# OperantFEDv9.net
KiCad netlist of a schematic drawn in EAGLE
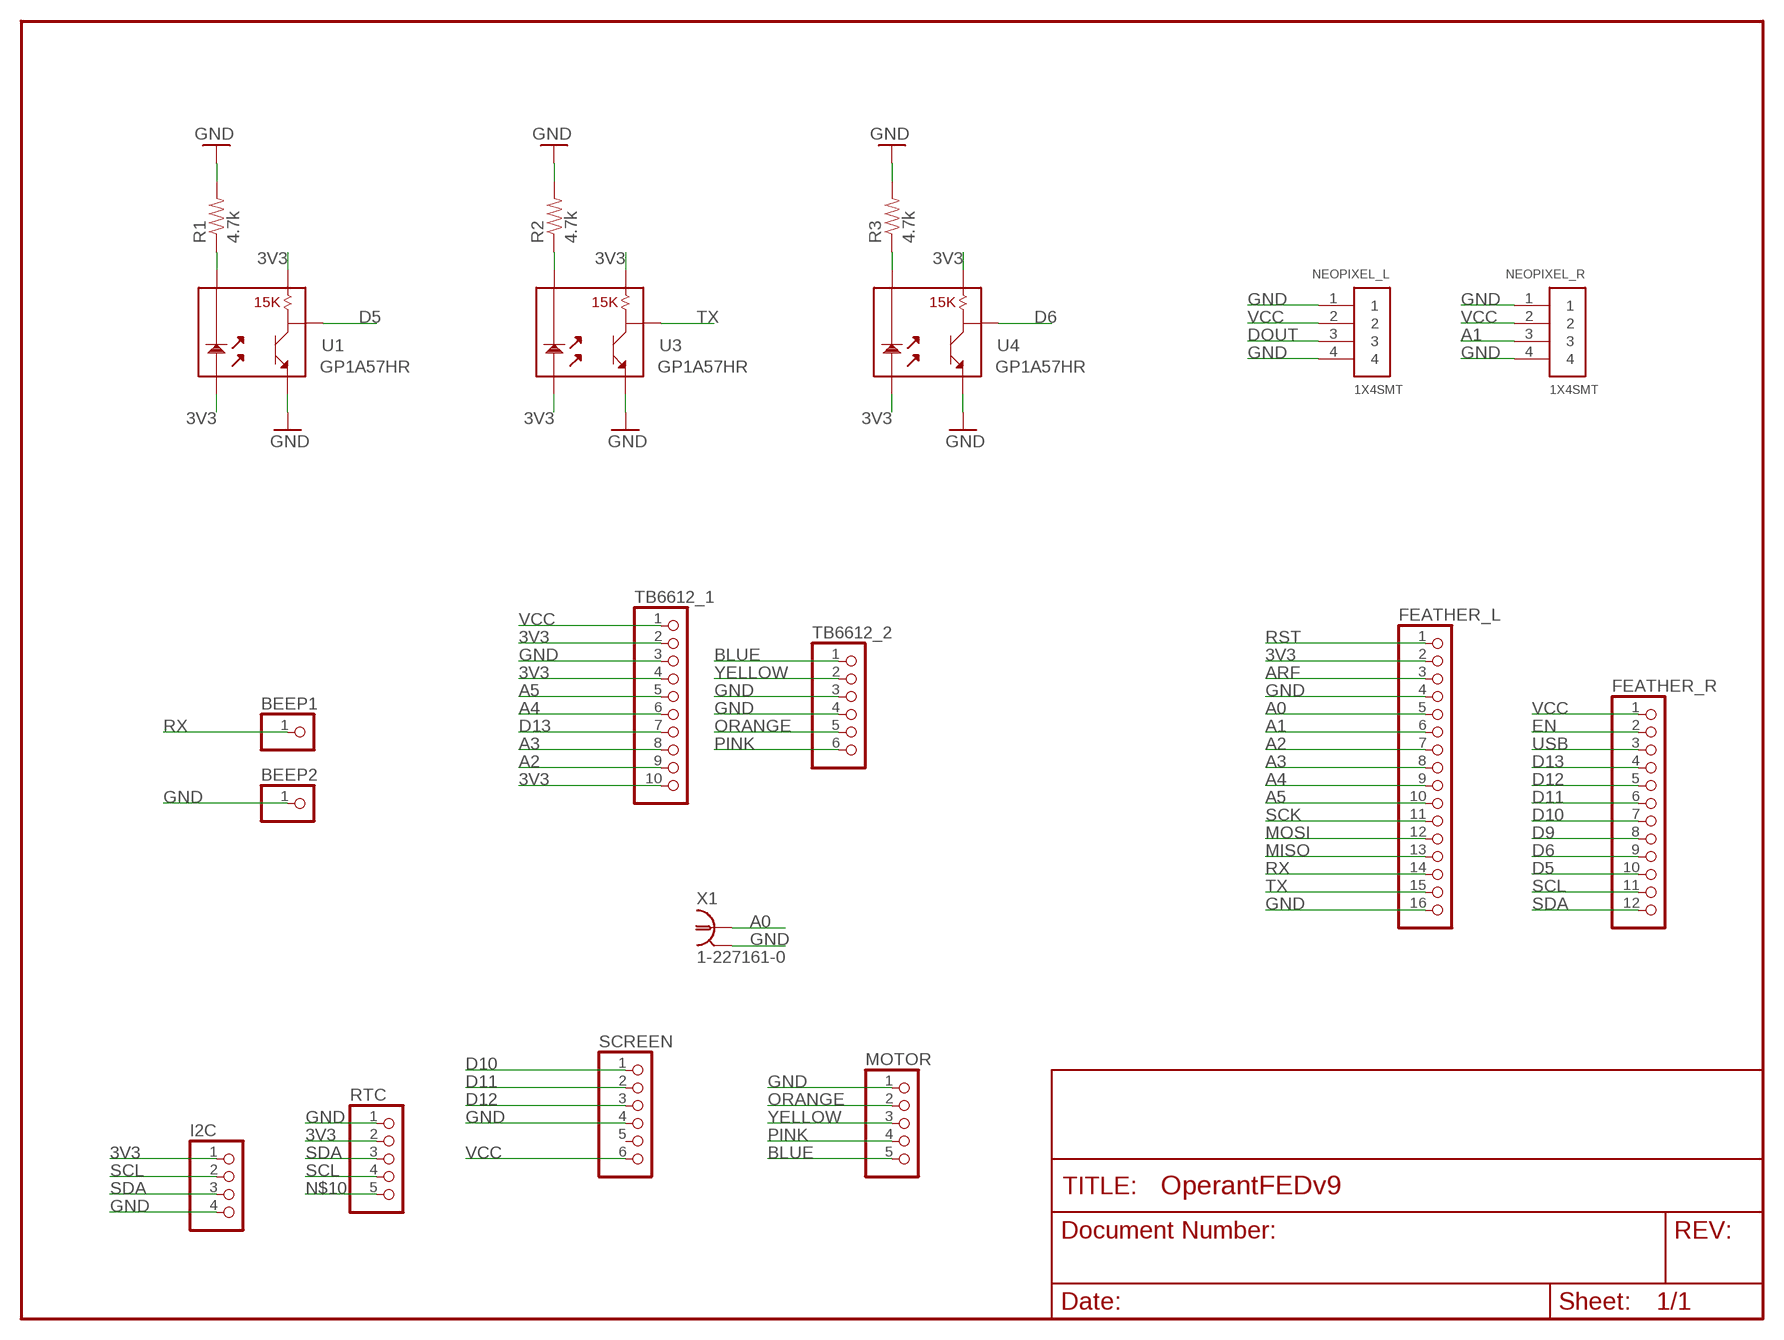
[diagram p0: schematic, sheet 1]

(export (version "E")
  (design (tool "Eeschema 10.0.6"))
  (components
    (comp (ref "BEEP1")
      (value "PINHD-1X1")
      (footprint "eagle-import:1X01")
      (libsource (lib "eagle-import") (part "PINHD-1X1"))
    )
    (comp (ref "BEEP2")
      (value "PINHD-1X1")
      (footprint "eagle-import:1X01")
      (libsource (lib "eagle-import") (part "PINHD-1X1"))
    )
    (comp (ref "FEATHER_L")
      (value "PINHD-1X16")
      (footprint "eagle-import:1X16")
      (libsource (lib "eagle-import") (part "PINHD-1X16"))
    )
    (comp (ref "FEATHER_R")
      (value "PINHD-1X12")
      (footprint "eagle-import:1X12")
      (libsource (lib "eagle-import") (part "PINHD-1X12"))
    )
    (comp (ref "I2C")
      (value "PINHD-1X4")
      (footprint "eagle-import:1X04")
      (libsource (lib "eagle-import") (part "PINHD-1X4"))
    )
    (comp (ref "MOTOR")
      (value "PINHD-1X5")
      (footprint "eagle-import:1X05")
      (libsource (lib "eagle-import") (part "PINHD-1X5"))
    )
    (comp (ref "NEOPIXEL_L")
      (value "1X4SMT")
      (footprint "eagle-import:1X4-SMT")
      (libsource (lib "eagle-import") (part "1X4SMT"))
    )
    (comp (ref "NEOPIXEL_R")
      (value "1X4SMT")
      (footprint "eagle-import:1X4-SMT")
      (libsource (lib "eagle-import") (part "1X4SMT"))
    )
    (comp (ref "R1")
      (value "4.7k")
      (footprint "eagle-import:AXIAL-0.3")
      (libsource (lib "eagle-import") (part "RESISTORPTH1"))
    )
    (comp (ref "R2")
      (value "4.7k")
      (footprint "eagle-import:AXIAL-0.3")
      (libsource (lib "eagle-import") (part "RESISTORPTH1"))
    )
    (comp (ref "R3")
      (value "4.7k")
      (footprint "eagle-import:AXIAL-0.3")
      (libsource (lib "eagle-import") (part "RESISTORPTH1"))
    )
    (comp (ref "RTC")
      (value "PINHD-1X5")
      (footprint "eagle-import:1X05")
      (libsource (lib "eagle-import") (part "PINHD-1X5"))
    )
    (comp (ref "SCREEN")
      (value "PINHD-1X6")
      (footprint "eagle-import:1X06")
      (libsource (lib "eagle-import") (part "PINHD-1X6"))
    )
    (comp (ref "TB6612_1")
      (value "PINHD-1X10")
      (footprint "eagle-import:1X10")
      (libsource (lib "eagle-import") (part "PINHD-1X10"))
    )
    (comp (ref "TB6612_2")
      (value "PINHD-1X6")
      (footprint "eagle-import:1X06")
      (libsource (lib "eagle-import") (part "PINHD-1X6"))
    )
    (comp (ref "U1")
      (value "GP1A57HR")
      (footprint "eagle-import:GP1A57HR")
      (libsource (lib "eagle-import") (part "GP1A57HR"))
    )
    (comp (ref "U3")
      (value "GP1A57HR")
      (footprint "eagle-import:GP1A57HR")
      (libsource (lib "eagle-import") (part "GP1A57HR"))
    )
    (comp (ref "U4")
      (value "GP1A57HR")
      (footprint "eagle-import:GP1A57HR")
      (libsource (lib "eagle-import") (part "GP1A57HR"))
    )
    (comp (ref "X1")
      (value "1-227161-0")
      (footprint "eagle-import:AMP_227161")
      (fields (field (name "MF") "TYCO ELECTRONICS") (field (name "MPN") "1-227161"))
      (libsource (lib "eagle-import") (part "?2271611--0"))
    )
  )
  (nets
    (net (code "1") (name "/3V3") (class "Default")
      (node (ref "FEATHER_L") (pin "2") (pinfunction "2_2") (pintype "passive"))
      (node (ref "I2C") (pin "1") (pinfunction "1_1") (pintype "passive"))
      (node (ref "RTC") (pin "2") (pinfunction "2_2") (pintype "passive"))
      (node (ref "TB6612_1") (pin "10") (pinfunction "10_10") (pintype "passive"))
      (node (ref "TB6612_1") (pin "2") (pinfunction "2_2") (pintype "passive"))
      (node (ref "TB6612_1") (pin "4") (pinfunction "4_4") (pintype "passive"))
      (node (ref "U1") (pin "1") (pinfunction "1_1") (pintype "bidirectional"))
      (node (ref "U1") (pin "3") (pinfunction "3_3") (pintype "bidirectional"))
      (node (ref "U3") (pin "1") (pinfunction "1_1") (pintype "bidirectional"))
      (node (ref "U3") (pin "3") (pinfunction "3_3") (pintype "bidirectional"))
      (node (ref "U4") (pin "1") (pinfunction "1_1") (pintype "bidirectional"))
      (node (ref "U4") (pin "3") (pinfunction "3_3") (pintype "bidirectional"))
    )
    (net (code "2") (name "/A0") (class "Default")
      (node (ref "FEATHER_L") (pin "5") (pinfunction "5_5") (pintype "passive"))
      (node (ref "X1") (pin "1") (pinfunction "1_1") (pintype "passive"))
    )
    (net (code "3") (name "/A1") (class "Default")
      (node (ref "FEATHER_L") (pin "6") (pinfunction "6_6") (pintype "passive"))
      (node (ref "NEOPIXEL_R") (pin "3") (pinfunction "3_3") (pintype "bidirectional"))
    )
    (net (code "4") (name "/A2") (class "Default")
      (node (ref "FEATHER_L") (pin "7") (pinfunction "7_7") (pintype "passive"))
      (node (ref "TB6612_1") (pin "9") (pinfunction "9_9") (pintype "passive"))
    )
    (net (code "5") (name "/A3") (class "Default")
      (node (ref "FEATHER_L") (pin "8") (pinfunction "8_8") (pintype "passive"))
      (node (ref "TB6612_1") (pin "8") (pinfunction "8_8") (pintype "passive"))
    )
    (net (code "6") (name "/A4") (class "Default")
      (node (ref "FEATHER_L") (pin "9") (pinfunction "9_9") (pintype "passive"))
      (node (ref "TB6612_1") (pin "6") (pinfunction "6_6") (pintype "passive"))
    )
    (net (code "7") (name "/A5") (class "Default")
      (node (ref "FEATHER_L") (pin "10") (pinfunction "10_10") (pintype "passive"))
      (node (ref "TB6612_1") (pin "5") (pinfunction "5_5") (pintype "passive"))
    )
    (net (code "8") (name "/ARF") (class "Default")
      (node (ref "FEATHER_L") (pin "3") (pinfunction "3_3") (pintype "passive"))
    )
    (net (code "9") (name "/BLUE") (class "Default")
      (node (ref "MOTOR") (pin "5") (pinfunction "5_5") (pintype "passive"))
      (node (ref "TB6612_2") (pin "1") (pinfunction "1_1") (pintype "passive"))
    )
    (net (code "10") (name "/D5") (class "Default")
      (node (ref "FEATHER_R") (pin "10") (pinfunction "10_10") (pintype "passive"))
      (node (ref "U1") (pin "4") (pinfunction "4_4") (pintype "bidirectional"))
    )
    (net (code "11") (name "/D6") (class "Default")
      (node (ref "FEATHER_R") (pin "9") (pinfunction "9_9") (pintype "passive"))
      (node (ref "U4") (pin "4") (pinfunction "4_4") (pintype "bidirectional"))
    )
    (net (code "12") (name "/D9") (class "Default")
      (node (ref "FEATHER_R") (pin "8") (pinfunction "8_8") (pintype "passive"))
    )
    (net (code "13") (name "/D10") (class "Default")
      (node (ref "FEATHER_R") (pin "7") (pinfunction "7_7") (pintype "passive"))
      (node (ref "SCREEN") (pin "1") (pinfunction "1_1") (pintype "passive"))
    )
    (net (code "14") (name "/D11") (class "Default")
      (node (ref "FEATHER_R") (pin "6") (pinfunction "6_6") (pintype "passive"))
      (node (ref "SCREEN") (pin "2") (pinfunction "2_2") (pintype "passive"))
    )
    (net (code "15") (name "/D12") (class "Default")
      (node (ref "FEATHER_R") (pin "5") (pinfunction "5_5") (pintype "passive"))
      (node (ref "SCREEN") (pin "3") (pinfunction "3_3") (pintype "passive"))
    )
    (net (code "16") (name "/D13") (class "Default")
      (node (ref "FEATHER_R") (pin "4") (pinfunction "4_4") (pintype "passive"))
      (node (ref "TB6612_1") (pin "7") (pinfunction "7_7") (pintype "passive"))
    )
    (net (code "17") (name "/DOUT") (class "Default")
      (node (ref "NEOPIXEL_L") (pin "3") (pinfunction "3_3") (pintype "bidirectional"))
    )
    (net (code "18") (name "/EN") (class "Default")
      (node (ref "FEATHER_R") (pin "2") (pinfunction "2_2") (pintype "passive"))
    )
    (net (code "19") (name "/MISO") (class "Default")
      (node (ref "FEATHER_L") (pin "13") (pinfunction "13_13") (pintype "passive"))
    )
    (net (code "20") (name "/MOSI") (class "Default")
      (node (ref "FEATHER_L") (pin "12") (pinfunction "12_12") (pintype "passive"))
    )
    (net (code "21") (name "/N$10") (class "Default")
      (node (ref "RTC") (pin "5") (pinfunction "5_5") (pintype "passive"))
    )
    (net (code "22") (name "/ORANGE") (class "Default")
      (node (ref "MOTOR") (pin "2") (pinfunction "2_2") (pintype "passive"))
      (node (ref "TB6612_2") (pin "5") (pinfunction "5_5") (pintype "passive"))
    )
    (net (code "23") (name "/PINK") (class "Default")
      (node (ref "MOTOR") (pin "4") (pinfunction "4_4") (pintype "passive"))
      (node (ref "TB6612_2") (pin "6") (pinfunction "6_6") (pintype "passive"))
    )
    (net (code "24") (name "/RST") (class "Default")
      (node (ref "FEATHER_L") (pin "1") (pinfunction "1_1") (pintype "passive"))
    )
    (net (code "25") (name "/RX") (class "Default")
      (node (ref "BEEP1") (pin "1") (pinfunction "1_1") (pintype "passive"))
      (node (ref "FEATHER_L") (pin "14") (pinfunction "14_14") (pintype "passive"))
    )
    (net (code "26") (name "/SCK") (class "Default")
      (node (ref "FEATHER_L") (pin "11") (pinfunction "11_11") (pintype "passive"))
    )
    (net (code "27") (name "/SCL") (class "Default")
      (node (ref "FEATHER_R") (pin "11") (pinfunction "11_11") (pintype "passive"))
      (node (ref "I2C") (pin "2") (pinfunction "2_2") (pintype "passive"))
      (node (ref "RTC") (pin "4") (pinfunction "4_4") (pintype "passive"))
    )
    (net (code "28") (name "/SDA") (class "Default")
      (node (ref "FEATHER_R") (pin "12") (pinfunction "12_12") (pintype "passive"))
      (node (ref "I2C") (pin "3") (pinfunction "3_3") (pintype "passive"))
      (node (ref "RTC") (pin "3") (pinfunction "3_3") (pintype "passive"))
    )
    (net (code "29") (name "/TX") (class "Default")
      (node (ref "FEATHER_L") (pin "15") (pinfunction "15_15") (pintype "passive"))
      (node (ref "U3") (pin "4") (pinfunction "4_4") (pintype "bidirectional"))
    )
    (net (code "30") (name "/USB") (class "Default")
      (node (ref "FEATHER_R") (pin "3") (pinfunction "3_3") (pintype "passive"))
    )
    (net (code "31") (name "/VCC") (class "Default")
      (node (ref "FEATHER_R") (pin "1") (pinfunction "1_1") (pintype "passive"))
      (node (ref "NEOPIXEL_L") (pin "2") (pinfunction "2_2") (pintype "bidirectional"))
      (node (ref "NEOPIXEL_R") (pin "2") (pinfunction "2_2") (pintype "bidirectional"))
      (node (ref "SCREEN") (pin "6") (pinfunction "6_6") (pintype "passive"))
      (node (ref "TB6612_1") (pin "1") (pinfunction "1_1") (pintype "passive"))
    )
    (net (code "32") (name "/YELLOW") (class "Default")
      (node (ref "MOTOR") (pin "3") (pinfunction "3_3") (pintype "passive"))
      (node (ref "TB6612_2") (pin "2") (pinfunction "2_2") (pintype "passive"))
    )
    (net (code "33") (name "GND") (class "Default")
      (node (ref "BEEP2") (pin "1") (pinfunction "1_1") (pintype "passive"))
      (node (ref "FEATHER_L") (pin "16") (pinfunction "16_16") (pintype "passive"))
      (node (ref "FEATHER_L") (pin "4") (pinfunction "4_4") (pintype "passive"))
      (node (ref "I2C") (pin "4") (pinfunction "4_4") (pintype "passive"))
      (node (ref "MOTOR") (pin "1") (pinfunction "1_1") (pintype "passive"))
      (node (ref "NEOPIXEL_L") (pin "1") (pinfunction "1_1") (pintype "bidirectional"))
      (node (ref "NEOPIXEL_L") (pin "4") (pinfunction "4_4") (pintype "bidirectional"))
      (node (ref "NEOPIXEL_R") (pin "1") (pinfunction "1_1") (pintype "bidirectional"))
      (node (ref "NEOPIXEL_R") (pin "4") (pinfunction "4_4") (pintype "bidirectional"))
      (node (ref "R1") (pin "P$2") (pinfunction "2_P$2") (pintype "passive"))
      (node (ref "R2") (pin "P$2") (pinfunction "2_P$2") (pintype "passive"))
      (node (ref "R3") (pin "P$2") (pinfunction "2_P$2") (pintype "passive"))
      (node (ref "RTC") (pin "1") (pinfunction "1_1") (pintype "passive"))
      (node (ref "SCREEN") (pin "4") (pinfunction "4_4") (pintype "passive"))
      (node (ref "TB6612_1") (pin "3") (pinfunction "3_3") (pintype "passive"))
      (node (ref "TB6612_2") (pin "3") (pinfunction "3_3") (pintype "passive"))
      (node (ref "TB6612_2") (pin "4") (pinfunction "4_4") (pintype "passive"))
      (node (ref "U1") (pin "5") (pinfunction "5_5") (pintype "bidirectional"))
      (node (ref "U3") (pin "5") (pinfunction "5_5") (pintype "bidirectional"))
      (node (ref "U4") (pin "5") (pinfunction "5_5") (pintype "bidirectional"))
      (node (ref "X1") (pin "2") (pinfunction "2_2") (pintype "passive"))
    )
    (net (code "34") (name "Net-(R1-1)") (class "Default")
      (node (ref "R1") (pin "P$1") (pinfunction "1_P$1") (pintype "passive"))
      (node (ref "U1") (pin "2") (pinfunction "2_2") (pintype "bidirectional"))
    )
    (net (code "35") (name "Net-(R2-1)") (class "Default")
      (node (ref "R2") (pin "P$1") (pinfunction "1_P$1") (pintype "passive"))
      (node (ref "U3") (pin "2") (pinfunction "2_2") (pintype "bidirectional"))
    )
    (net (code "36") (name "Net-(R3-1)") (class "Default")
      (node (ref "R3") (pin "P$1") (pinfunction "1_P$1") (pintype "passive"))
      (node (ref "U4") (pin "2") (pinfunction "2_2") (pintype "bidirectional"))
    )
    (net (code "37") (name "unconnected-(SCREEN-Pad5)") (class "Default")
      (node (ref "SCREEN") (pin "5") (pinfunction "5_5") (pintype "passive"))
    )
  )
)
